# main.net
KiCad netlist of a schematic drawn in Altium Designer
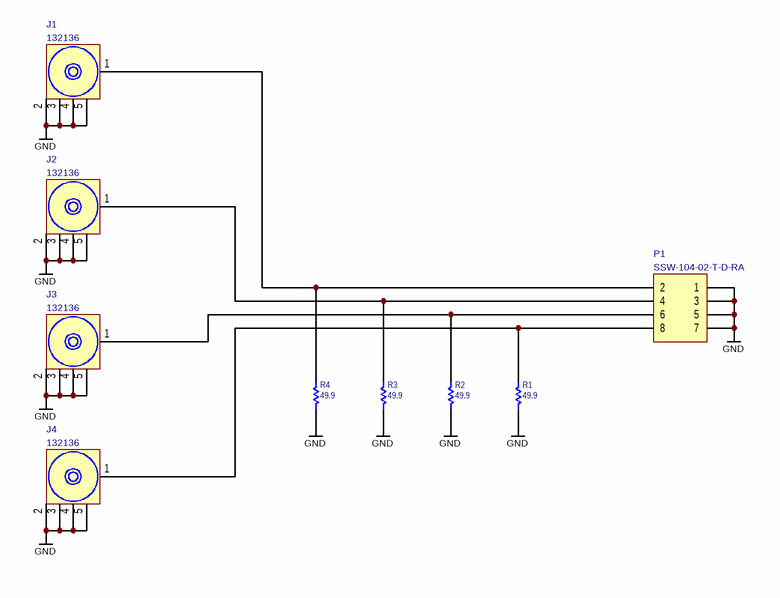
[diagram p0: main.SchDoc]

(export (version "E")
  (design (tool "Eeschema 10.0.6"))
  (components
    (comp (ref "J1")
      (value "132136")
      (footprint "132136")
      (description "SMA Right Angle Connector COAX Female")
      (fields (field (name "MANUFACTURER") "Amphenol"))
      (libsource (lib "amphenol") (part "132136"))
    )
    (comp (ref "J2")
      (value "132136")
      (footprint "132136")
      (description "SMA Right Angle Connector COAX Female")
      (fields (field (name "MANUFACTURER") "Amphenol"))
      (libsource (lib "amphenol") (part "132136"))
    )
    (comp (ref "J3")
      (value "132136")
      (footprint "132136")
      (description "SMA Right Angle Connector COAX Female")
      (fields (field (name "MANUFACTURER") "Amphenol"))
      (libsource (lib "amphenol") (part "132136"))
    )
    (comp (ref "J4")
      (value "132136")
      (footprint "132136")
      (description "SMA Right Angle Connector COAX Female")
      (fields (field (name "MANUFACTURER") "Amphenol"))
      (libsource (lib "amphenol") (part "132136"))
    )
    (comp (ref "P1")
      (value "SSW-104-02-T-D-RA")
      (footprint "samtec:SSW-104-02-T-D-RA")
      (description "Through Hole Right Angle 0.1\"-Pitch Header Receptacle")
      (fields (field (name "MANUFACTURER") "Samtec"))
      (libsource (lib "samtec") (part "SSW-104-02-T-D-RA"))
    )
    (comp (ref "R1")
      (value "49.9")
      (footprint "RESC2012X70N")
      (description "Thick Film Resistor 49.9 ±1% 0805")
      (fields (field (name "MANUFACTURER") "Panasonic") (field (name "TOLERANCE") "±1%"))
      (libsource (lib "Graviton") (part "RES 0402"))
    )
    (comp (ref "R2")
      (value "49.9")
      (footprint "RESC2012X70N")
      (description "Thick Film Resistor 49.9 ±1% 0805")
      (fields (field (name "MANUFACTURER") "Panasonic") (field (name "TOLERANCE") "±1%"))
      (libsource (lib "Graviton") (part "RES 0402"))
    )
    (comp (ref "R3")
      (value "49.9")
      (footprint "RESC2012X70N")
      (description "Thick Film Resistor 49.9 ±1% 0805")
      (fields (field (name "MANUFACTURER") "Panasonic") (field (name "TOLERANCE") "±1%"))
      (libsource (lib "Graviton") (part "RES 0402"))
    )
    (comp (ref "R4")
      (value "49.9")
      (footprint "RESC2012X70N")
      (description "Thick Film Resistor 49.9 ±1% 0805")
      (fields (field (name "MANUFACTURER") "Panasonic") (field (name "TOLERANCE") "±1%"))
      (libsource (lib "Graviton") (part "RES 0402"))
    )
  )
  (nets
    (net (code "1") (name "GND") (class "Default")
      (node (ref "J1") (pin "2") (pinfunction "GND_2") (pintype "passive"))
      (node (ref "J1") (pin "3") (pinfunction "GND_3") (pintype "passive"))
      (node (ref "J1") (pin "4") (pinfunction "GND_4") (pintype "passive"))
      (node (ref "J1") (pin "5") (pinfunction "GND_5") (pintype "passive"))
      (node (ref "J2") (pin "2") (pinfunction "GND_2") (pintype "passive"))
      (node (ref "J2") (pin "3") (pinfunction "GND_3") (pintype "passive"))
      (node (ref "J2") (pin "4") (pinfunction "GND_4") (pintype "passive"))
      (node (ref "J2") (pin "5") (pinfunction "GND_5") (pintype "passive"))
      (node (ref "J3") (pin "2") (pinfunction "GND_2") (pintype "passive"))
      (node (ref "J3") (pin "3") (pinfunction "GND_3") (pintype "passive"))
      (node (ref "J3") (pin "4") (pinfunction "GND_4") (pintype "passive"))
      (node (ref "J3") (pin "5") (pinfunction "GND_5") (pintype "passive"))
      (node (ref "J4") (pin "2") (pinfunction "GND_2") (pintype "passive"))
      (node (ref "J4") (pin "3") (pinfunction "GND_3") (pintype "passive"))
      (node (ref "J4") (pin "4") (pinfunction "GND_4") (pintype "passive"))
      (node (ref "J4") (pin "5") (pinfunction "GND_5") (pintype "passive"))
      (node (ref "P1") (pin "1") (pinfunction "1_1") (pintype "passive"))
      (node (ref "P1") (pin "3") (pinfunction "3_3") (pintype "passive"))
      (node (ref "P1") (pin "5") (pinfunction "5_5") (pintype "passive"))
      (node (ref "P1") (pin "7") (pinfunction "7_7") (pintype "passive"))
      (node (ref "R1") (pin "2") (pinfunction "2_2") (pintype "passive"))
      (node (ref "R2") (pin "2") (pinfunction "2_2") (pintype "passive"))
      (node (ref "R3") (pin "2") (pinfunction "2_2") (pintype "passive"))
      (node (ref "R4") (pin "2") (pinfunction "2_2") (pintype "passive"))
    )
    (net (code "2") (name "Net-(J1-CENTER)") (class "Default")
      (node (ref "J1") (pin "1") (pinfunction "CENTER_1") (pintype "passive"))
      (node (ref "P1") (pin "2") (pinfunction "2_2") (pintype "passive"))
      (node (ref "R4") (pin "1") (pinfunction "1_1") (pintype "passive"))
    )
    (net (code "3") (name "Net-(J2-CENTER)") (class "Default")
      (node (ref "J2") (pin "1") (pinfunction "CENTER_1") (pintype "passive"))
      (node (ref "P1") (pin "4") (pinfunction "4_4") (pintype "passive"))
      (node (ref "R3") (pin "1") (pinfunction "1_1") (pintype "passive"))
    )
    (net (code "4") (name "Net-(J3-CENTER)") (class "Default")
      (node (ref "J3") (pin "1") (pinfunction "CENTER_1") (pintype "passive"))
      (node (ref "P1") (pin "6") (pinfunction "6_6") (pintype "passive"))
      (node (ref "R2") (pin "1") (pinfunction "1_1") (pintype "passive"))
    )
    (net (code "5") (name "Net-(J4-CENTER)") (class "Default")
      (node (ref "J4") (pin "1") (pinfunction "CENTER_1") (pintype "passive"))
      (node (ref "P1") (pin "8") (pinfunction "8_8") (pintype "passive"))
      (node (ref "R1") (pin "1") (pinfunction "1_1") (pintype "passive"))
    )
  )
)
